# Esquema_02_guilherme.net
KiCad netlist of a schematic drawn in EAGLE
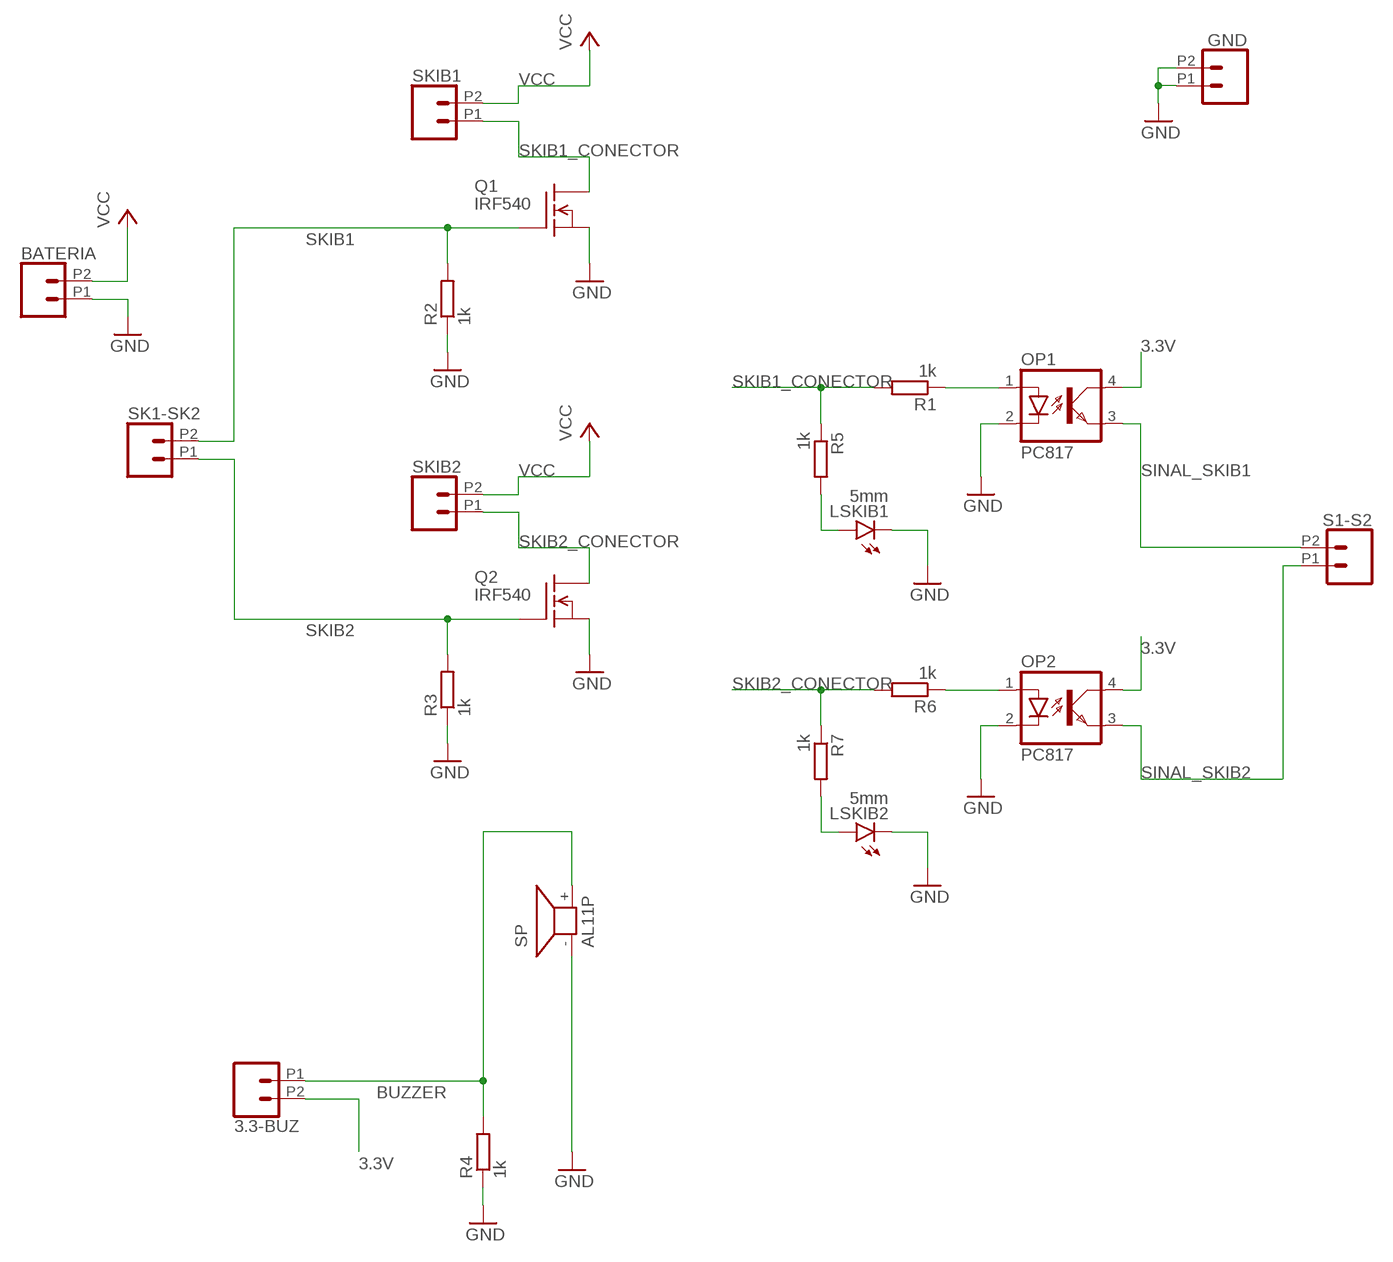
[diagram p0: schematic, sheet 1]

(export (version "E")
  (design (tool "Eeschema 10.0.6"))
  (components
    (comp (ref "3.3-BUZ")
      (value "CONN_022.54MM_SCREWTERM")
      (footprint "eagle-import:1X02_2.54_SCREWTERM")
      (libsource (lib "eagle-import") (part "CONN_022.54MM_SCREWTERM"))
    )
    (comp (ref "BATERIA")
      (value "CONN_022.54MM_SCREWTERM")
      (footprint "eagle-import:1X02_2.54_SCREWTERM")
      (libsource (lib "eagle-import") (part "CONN_022.54MM_SCREWTERM"))
    )
    (comp (ref "GND")
      (value "CONN_022.54MM_SCREWTERM")
      (footprint "eagle-import:1X02_2.54_SCREWTERM")
      (libsource (lib "eagle-import") (part "CONN_022.54MM_SCREWTERM"))
    )
    (comp (ref "LSKIB1")
      (value "5mm")
      (footprint "eagle-import:LED5MM")
      (libsource (lib "eagle-import") (part "LED5MM"))
    )
    (comp (ref "LSKIB2")
      (value "5mm")
      (footprint "eagle-import:LED5MM")
      (libsource (lib "eagle-import") (part "LED5MM"))
    )
    (comp (ref "OP1")
      (value "PC817")
      (footprint "eagle-import:DIL04")
      (fields (field (name "MPN") "PC817X4J000F"))
      (libsource (lib "eagle-import") (part "PC817"))
    )
    (comp (ref "OP2")
      (value "PC817")
      (footprint "eagle-import:DIL04")
      (fields (field (name "MPN") "PC817X4J000F"))
      (libsource (lib "eagle-import") (part "PC817"))
    )
    (comp (ref "Q1")
      (value "IRF540")
      (footprint "eagle-import:TO220")
      (libsource (lib "eagle-import") (part "IRF540"))
    )
    (comp (ref "Q2")
      (value "IRF540")
      (footprint "eagle-import:TO220")
      (libsource (lib "eagle-import") (part "IRF540"))
    )
    (comp (ref "R1")
      (value "1k")
      (footprint "eagle-import:0207_10")
      (libsource (lib "eagle-import") (part "R-EU_0207/10"))
    )
    (comp (ref "R2")
      (value "1k")
      (footprint "eagle-import:0207_10")
      (libsource (lib "eagle-import") (part "R-EU_0207/10"))
    )
    (comp (ref "R3")
      (value "1k")
      (footprint "eagle-import:0207_10")
      (libsource (lib "eagle-import") (part "R-EU_0207/10"))
    )
    (comp (ref "R4")
      (value "1k")
      (footprint "eagle-import:0207_10")
      (libsource (lib "eagle-import") (part "R-EU_0207/10"))
    )
    (comp (ref "R5")
      (value "1k")
      (footprint "eagle-import:0207_10")
      (libsource (lib "eagle-import") (part "R-EU_0207/10"))
    )
    (comp (ref "R6")
      (value "1k")
      (footprint "eagle-import:0207_10")
      (libsource (lib "eagle-import") (part "R-EU_0207/10"))
    )
    (comp (ref "R7")
      (value "1k")
      (footprint "eagle-import:0207_10")
      (libsource (lib "eagle-import") (part "R-EU_0207/10"))
    )
    (comp (ref "S1-S2")
      (value "CONN_022.54MM_SCREWTERM")
      (footprint "eagle-import:1X02_2.54_SCREWTERM")
      (libsource (lib "eagle-import") (part "CONN_022.54MM_SCREWTERM"))
    )
    (comp (ref "SK1-SK2")
      (value "CONN_022.54MM_SCREWTERM")
      (footprint "eagle-import:1X02_2.54_SCREWTERM")
      (libsource (lib "eagle-import") (part "CONN_022.54MM_SCREWTERM"))
    )
    (comp (ref "SKIB1")
      (value "CONN_022.54MM_SCREWTERM")
      (footprint "eagle-import:1X02_2.54_SCREWTERM")
      (libsource (lib "eagle-import") (part "CONN_022.54MM_SCREWTERM"))
    )
    (comp (ref "SKIB2")
      (value "CONN_022.54MM_SCREWTERM")
      (footprint "eagle-import:1X02_2.54_SCREWTERM")
      (libsource (lib "eagle-import") (part "CONN_022.54MM_SCREWTERM"))
    )
    (comp (ref "SP")
      (value "AL11P")
      (footprint "eagle-import:AL11P")
      (libsource (lib "eagle-import") (part "AL11P"))
    )
  )
  (nets
    (net (code "1") (name "/3.3V") (class "Default")
      (node (ref "3.3-BUZ") (pin "P2") (pinfunction "2_P2") (pintype "passive"))
      (node (ref "OP1") (pin "4") (pinfunction "COL_4") (pintype "passive"))
      (node (ref "OP2") (pin "4") (pinfunction "COL_4") (pintype "passive"))
    )
    (net (code "2") (name "/BUZZER") (class "Default")
      (node (ref "3.3-BUZ") (pin "P1") (pinfunction "1_P1") (pintype "passive"))
      (node (ref "R4") (pin "2") (pinfunction "2_2") (pintype "passive"))
      (node (ref "SP") (pin "+") (pinfunction "2_+") (pintype "passive"))
    )
    (net (code "3") (name "/SINAL_SKIB1") (class "Default")
      (node (ref "OP1") (pin "3") (pinfunction "EMIT_3") (pintype "passive"))
      (node (ref "S1-S2") (pin "P2") (pinfunction "2_P2") (pintype "passive"))
    )
    (net (code "4") (name "/SINAL_SKIB2") (class "Default")
      (node (ref "OP2") (pin "3") (pinfunction "EMIT_3") (pintype "passive"))
      (node (ref "S1-S2") (pin "P1") (pinfunction "1_P1") (pintype "passive"))
    )
    (net (code "5") (name "/SKIB1") (class "Default")
      (node (ref "Q1") (pin "1") (pinfunction "G_1") (pintype "passive"))
      (node (ref "R2") (pin "2") (pinfunction "2_2") (pintype "passive"))
      (node (ref "SK1-SK2") (pin "P2") (pinfunction "2_P2") (pintype "passive"))
    )
    (net (code "6") (name "/SKIB1_CONECTOR") (class "Default")
      (node (ref "Q1") (pin "2") (pinfunction "D_2") (pintype "passive"))
      (node (ref "R1") (pin "2") (pinfunction "2_2") (pintype "passive"))
      (node (ref "R5") (pin "1") (pinfunction "1_1") (pintype "passive"))
      (node (ref "SKIB1") (pin "P1") (pinfunction "1_P1") (pintype "passive"))
    )
    (net (code "7") (name "/SKIB2") (class "Default")
      (node (ref "Q2") (pin "1") (pinfunction "G_1") (pintype "passive"))
      (node (ref "R3") (pin "2") (pinfunction "2_2") (pintype "passive"))
      (node (ref "SK1-SK2") (pin "P1") (pinfunction "1_P1") (pintype "passive"))
    )
    (net (code "8") (name "/SKIB2_CONECTOR") (class "Default")
      (node (ref "Q2") (pin "2") (pinfunction "D_2") (pintype "passive"))
      (node (ref "R6") (pin "2") (pinfunction "2_2") (pintype "passive"))
      (node (ref "R7") (pin "1") (pinfunction "1_1") (pintype "passive"))
      (node (ref "SKIB2") (pin "P1") (pinfunction "1_P1") (pintype "passive"))
    )
    (net (code "9") (name "GND") (class "Default")
      (node (ref "BATERIA") (pin "P1") (pinfunction "1_P1") (pintype "passive"))
      (node (ref "GND") (pin "P1") (pinfunction "1_P1") (pintype "passive"))
      (node (ref "GND") (pin "P2") (pinfunction "2_P2") (pintype "passive"))
      (node (ref "LSKIB1") (pin "K") (pinfunction "C_K") (pintype "passive"))
      (node (ref "LSKIB2") (pin "K") (pinfunction "C_K") (pintype "passive"))
      (node (ref "OP1") (pin "2") (pinfunction "C_2") (pintype "passive"))
      (node (ref "OP2") (pin "2") (pinfunction "C_2") (pintype "passive"))
      (node (ref "Q1") (pin "3") (pinfunction "S_3") (pintype "passive"))
      (node (ref "Q2") (pin "3") (pinfunction "S_3") (pintype "passive"))
      (node (ref "R2") (pin "1") (pinfunction "1_1") (pintype "passive"))
      (node (ref "R3") (pin "1") (pinfunction "1_1") (pintype "passive"))
      (node (ref "R4") (pin "1") (pinfunction "1_1") (pintype "passive"))
      (node (ref "SP") (pin "-") (pinfunction "1_-") (pintype "passive"))
    )
    (net (code "10") (name "Net-(LSKIB1-PadA)") (class "Default")
      (node (ref "LSKIB1") (pin "A") (pinfunction "A_A") (pintype "passive"))
      (node (ref "R5") (pin "2") (pinfunction "2_2") (pintype "passive"))
    )
    (net (code "11") (name "Net-(LSKIB2-PadA)") (class "Default")
      (node (ref "LSKIB2") (pin "A") (pinfunction "A_A") (pintype "passive"))
      (node (ref "R7") (pin "2") (pinfunction "2_2") (pintype "passive"))
    )
    (net (code "12") (name "Net-(OP1-A)") (class "Default")
      (node (ref "OP1") (pin "1") (pinfunction "A_1") (pintype "passive"))
      (node (ref "R1") (pin "1") (pinfunction "1_1") (pintype "passive"))
    )
    (net (code "13") (name "Net-(OP2-A)") (class "Default")
      (node (ref "OP2") (pin "1") (pinfunction "A_1") (pintype "passive"))
      (node (ref "R6") (pin "1") (pinfunction "1_1") (pintype "passive"))
    )
    (net (code "14") (name "VCC") (class "Default")
      (node (ref "BATERIA") (pin "P2") (pinfunction "2_P2") (pintype "passive"))
      (node (ref "SKIB1") (pin "P2") (pinfunction "2_P2") (pintype "passive"))
      (node (ref "SKIB2") (pin "P2") (pinfunction "2_P2") (pintype "passive"))
    )
  )
)
